# ProjectSchematic_v28.net
KiCad netlist of a schematic drawn in EAGLE
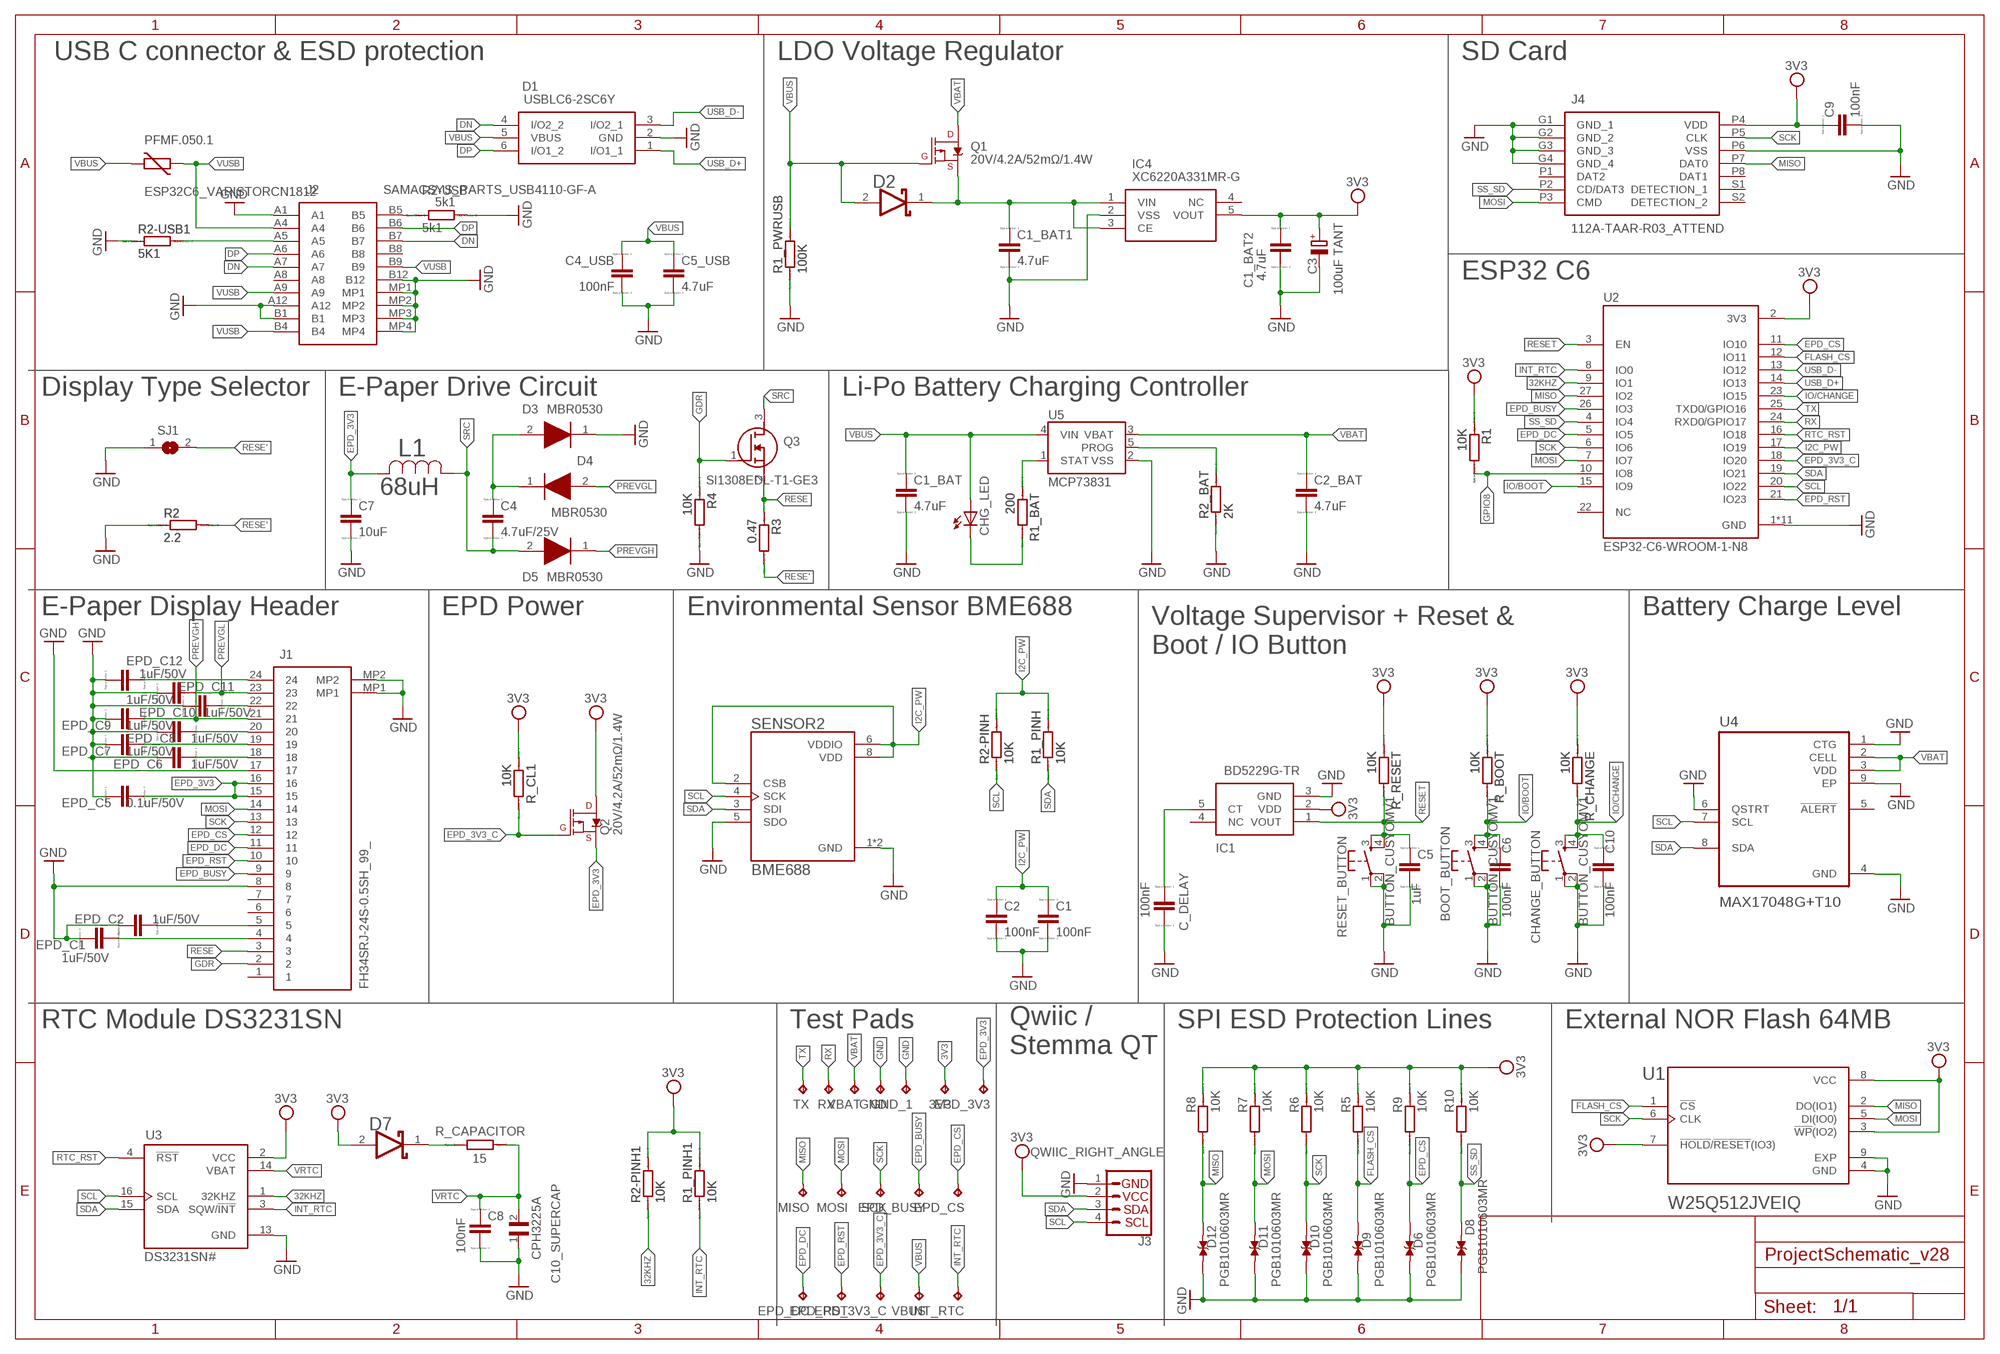
[diagram p0: schematic, sheet 1]

(export (version "E")
  (design (tool "Eeschema 10.0.6"))
  (components
    (comp (ref "3V3")
      (value "TPTP20R")
      (footprint "eagle-import:TP20R")
      (libsource (lib "eagle-import") (part "TPTP20R"))
    )
    (comp (ref "BOOT_BUTTON")
      (value "BUTTON_CUSYOMV1")
      (footprint "eagle-import:MYBUTTON")
      (libsource (lib "eagle-import") (part "BUTTON_CUSYOMV1"))
    )
    (comp (ref "C1")
      (value "100nF")
      (footprint "eagle-import:ESP32_WROVER_EAGLE-LTSPICE_C0402")
      (libsource (lib "eagle-import") (part "ESP32_WROVER_EAGLE-LTSPICE_CC0402"))
    )
    (comp (ref "C1_BAT")
      (value "4.7uF")
      (footprint "eagle-import:ESP32_WROVER_EAGLE-LTSPICE_C0402")
      (libsource (lib "eagle-import") (part "ESP32_WROVER_EAGLE-LTSPICE_CC0402"))
    )
    (comp (ref "C1_BAT1")
      (value "4.7uF")
      (footprint "eagle-import:ESP32_WROVER_EAGLE-LTSPICE_C0402")
      (libsource (lib "eagle-import") (part "ESP32_WROVER_EAGLE-LTSPICE_CC0402"))
    )
    (comp (ref "C1_BAT2")
      (value "4.7uF")
      (footprint "eagle-import:ESP32_WROVER_EAGLE-LTSPICE_C0402")
      (libsource (lib "eagle-import") (part "ESP32_WROVER_EAGLE-LTSPICE_CC0402"))
    )
    (comp (ref "C2")
      (value "100nF")
      (footprint "eagle-import:ESP32_WROVER_EAGLE-LTSPICE_C0402")
      (libsource (lib "eagle-import") (part "ESP32_WROVER_EAGLE-LTSPICE_CC0402"))
    )
    (comp (ref "C2_BAT")
      (value "4.7uF")
      (footprint "eagle-import:ESP32_WROVER_EAGLE-LTSPICE_C0402")
      (libsource (lib "eagle-import") (part "ESP32_WROVER_EAGLE-LTSPICE_CC0402"))
    )
    (comp (ref "C3")
      (value "100uF TANT")
      (footprint "eagle-import:RCL_CT3528")
      (libsource (lib "eagle-import") (part "RCL_CPOL-EUCT3528"))
    )
    (comp (ref "C4")
      (value "4.7uF/25V")
      (footprint "eagle-import:ESP32_WROVER_EAGLE-LTSPICE_C0402")
      (libsource (lib "eagle-import") (part "ESP32_WROVER_EAGLE-LTSPICE_CC0402"))
    )
    (comp (ref "C4_USB")
      (value "100nF")
      (footprint "eagle-import:ESP32_WROVER_EAGLE-LTSPICE_C0402")
      (libsource (lib "eagle-import") (part "ESP32_WROVER_EAGLE-LTSPICE_CC0402"))
    )
    (comp (ref "C5")
      (value "1uF")
      (footprint "eagle-import:ESP32_WROVER_EAGLE-LTSPICE_C0402")
      (libsource (lib "eagle-import") (part "ESP32_WROVER_EAGLE-LTSPICE_CC0402"))
    )
    (comp (ref "C5_USB")
      (value "4.7uF")
      (footprint "eagle-import:ESP32_WROVER_EAGLE-LTSPICE_C0402")
      (libsource (lib "eagle-import") (part "ESP32_WROVER_EAGLE-LTSPICE_CC0402"))
    )
    (comp (ref "C6")
      (value "100nF")
      (footprint "eagle-import:ESP32_WROVER_EAGLE-LTSPICE_C0402")
      (libsource (lib "eagle-import") (part "ESP32_WROVER_EAGLE-LTSPICE_CC0402"))
    )
    (comp (ref "C7")
      (value "10uF")
      (footprint "eagle-import:ESP32_WROVER_EAGLE-LTSPICE_C0402")
      (libsource (lib "eagle-import") (part "ESP32_WROVER_EAGLE-LTSPICE_CC0402"))
    )
    (comp (ref "C8")
      (value "100nF")
      (footprint "eagle-import:ESP32_WROVER_EAGLE-LTSPICE_C0402")
      (libsource (lib "eagle-import") (part "ESP32_WROVER_EAGLE-LTSPICE_CC0402"))
    )
    (comp (ref "C9")
      (value "100nF")
      (footprint "eagle-import:ESP32_WROVER_EAGLE-LTSPICE_C0402")
      (libsource (lib "eagle-import") (part "ESP32_WROVER_EAGLE-LTSPICE_CC0402"))
    )
    (comp (ref "C10")
      (value "100nF")
      (footprint "eagle-import:ESP32_WROVER_EAGLE-LTSPICE_C0402")
      (libsource (lib "eagle-import") (part "ESP32_WROVER_EAGLE-LTSPICE_CC0402"))
    )
    (comp (ref "C10_SUPERCAP")
      (value "CPH3225A")
      (footprint "eagle-import:CAPCP3225X100N")
      (fields (field (name "MF") "Seiko Instruments"))
      (libsource (lib "eagle-import") (part "CPH3225A"))
    )
    (comp (ref "CHANGE_BUTTON")
      (value "BUTTON_CUSYOMV1")
      (footprint "eagle-import:MYBUTTON")
      (libsource (lib "eagle-import") (part "BUTTON_CUSYOMV1"))
    )
    (comp (ref "CHG_LED")
      (value "ADAFRUIT_LEDCHIP-LED0603")
      (footprint "eagle-import:ADAFRUIT_CHIP-LED0603")
      (libsource (lib "eagle-import") (part "ADAFRUIT_LEDCHIP-LED0603"))
    )
    (comp (ref "C_DELAY")
      (value "100nF")
      (footprint "eagle-import:ESP32_WROVER_EAGLE-LTSPICE_C0402")
      (libsource (lib "eagle-import") (part "ESP32_WROVER_EAGLE-LTSPICE_CC0402"))
    )
    (comp (ref "D1")
      (value "USBLC6-2SC6Y")
      (footprint "eagle-import:SOT95P280X145-6N")
      (fields (field (name "MF") "STMicroelectronics"))
      (libsource (lib "eagle-import") (part "USBLC6-2SC6Y"))
    )
    (comp (ref "D2")
      (value "ESP32_WROVER_AVX---SD0805S020S1R0_AVX_SD0805S020S1R0_0_0AVX_SD0805S020S1R0_0_0")
      (footprint "eagle-import:ESP32_WROVER_AVX---SD0805S020S1R0_AVX_SD0805S020S1R0_0")
      (fields
        (field (name "DIGIKEY_PART_NUMBER") "478-7800-1-ND")
        (field (name "MF") "AVX")
        (field (name "MOUSER_PART_NUMBER") "581-SD0805S020S1R0")
      )
      (libsource (lib "eagle-import") (part "ESP32_WROVER_AVX---SD0805S020S1R0_AVX_SD0805S020S1R0_0_0AVX_SD0805S020S1R0_0_0"))
    )
    (comp (ref "D3")
      (value "MBR0530")
      (footprint "eagle-import:SOD3716X135N")
      (fields (field (name "MF") "ON Semiconductor"))
      (libsource (lib "eagle-import") (part "MBR0530"))
    )
    (comp (ref "D4")
      (value "MBR0530")
      (footprint "eagle-import:SOD3716X135N")
      (fields (field (name "MF") "ON Semiconductor"))
      (libsource (lib "eagle-import") (part "MBR0530"))
    )
    (comp (ref "D5")
      (value "MBR0530")
      (footprint "eagle-import:SOD3716X135N")
      (fields (field (name "MF") "ON Semiconductor"))
      (libsource (lib "eagle-import") (part "MBR0530"))
    )
    (comp (ref "D6")
      (value "PGB1010603MR")
      (footprint "eagle-import:DIOC1608X36N")
      (fields (field (name "MF") "Littelfuse Inc."))
      (libsource (lib "eagle-import") (part "PGB1010603MR"))
    )
    (comp (ref "D7")
      (value "ESP32_WROVER_AVX---SD0805S020S1R0_AVX_SD0805S020S1R0_0_0AVX_SD0805S020S1R0_0_0")
      (footprint "eagle-import:ESP32_WROVER_AVX---SD0805S020S1R0_AVX_SD0805S020S1R0_0")
      (fields
        (field (name "DIGIKEY_PART_NUMBER") "478-7800-1-ND")
        (field (name "MF") "AVX")
        (field (name "MOUSER_PART_NUMBER") "581-SD0805S020S1R0")
      )
      (libsource (lib "eagle-import") (part "ESP32_WROVER_AVX---SD0805S020S1R0_AVX_SD0805S020S1R0_0_0AVX_SD0805S020S1R0_0_0"))
    )
    (comp (ref "D8")
      (value "PGB1010603MR")
      (footprint "eagle-import:DIOC1608X36N")
      (fields (field (name "MF") "Littelfuse Inc."))
      (libsource (lib "eagle-import") (part "PGB1010603MR"))
    )
    (comp (ref "D9")
      (value "PGB1010603MR")
      (footprint "eagle-import:DIOC1608X36N")
      (fields (field (name "MF") "Littelfuse Inc."))
      (libsource (lib "eagle-import") (part "PGB1010603MR"))
    )
    (comp (ref "D10")
      (value "PGB1010603MR")
      (footprint "eagle-import:DIOC1608X36N")
      (fields (field (name "MF") "Littelfuse Inc."))
      (libsource (lib "eagle-import") (part "PGB1010603MR"))
    )
    (comp (ref "D11")
      (value "PGB1010603MR")
      (footprint "eagle-import:DIOC1608X36N")
      (fields (field (name "MF") "Littelfuse Inc."))
      (libsource (lib "eagle-import") (part "PGB1010603MR"))
    )
    (comp (ref "D12")
      (value "PGB1010603MR")
      (footprint "eagle-import:DIOC1608X36N")
      (fields (field (name "MF") "Littelfuse Inc."))
      (libsource (lib "eagle-import") (part "PGB1010603MR"))
    )
    (comp (ref "EPD_3V3")
      (value "TPTP20R")
      (footprint "eagle-import:TP20R")
      (libsource (lib "eagle-import") (part "TPTP20R"))
    )
    (comp (ref "EPD_3V3_C")
      (value "TPTP20R")
      (footprint "eagle-import:TP20R")
      (libsource (lib "eagle-import") (part "TPTP20R"))
    )
    (comp (ref "EPD_BUSY")
      (value "TPTP20R")
      (footprint "eagle-import:TP20R")
      (libsource (lib "eagle-import") (part "TPTP20R"))
    )
    (comp (ref "EPD_C1")
      (value "1uF/50V")
      (footprint "eagle-import:ESP32_WROVER_EAGLE-LTSPICE_C0402")
      (libsource (lib "eagle-import") (part "ESP32_WROVER_EAGLE-LTSPICE_CC0402"))
    )
    (comp (ref "EPD_C2")
      (value "1uF/50V")
      (footprint "eagle-import:ESP32_WROVER_EAGLE-LTSPICE_C0402")
      (libsource (lib "eagle-import") (part "ESP32_WROVER_EAGLE-LTSPICE_CC0402"))
    )
    (comp (ref "EPD_C5")
      (value "0.1uF/50V")
      (footprint "eagle-import:ESP32_WROVER_EAGLE-LTSPICE_C0402")
      (libsource (lib "eagle-import") (part "ESP32_WROVER_EAGLE-LTSPICE_CC0402"))
    )
    (comp (ref "EPD_C6")
      (value "1uF/50V")
      (footprint "eagle-import:ESP32_WROVER_EAGLE-LTSPICE_C0402")
      (libsource (lib "eagle-import") (part "ESP32_WROVER_EAGLE-LTSPICE_CC0402"))
    )
    (comp (ref "EPD_C7")
      (value "1uF/50V")
      (footprint "eagle-import:ESP32_WROVER_EAGLE-LTSPICE_C0402")
      (libsource (lib "eagle-import") (part "ESP32_WROVER_EAGLE-LTSPICE_CC0402"))
    )
    (comp (ref "EPD_C8")
      (value "1uF/50V")
      (footprint "eagle-import:ESP32_WROVER_EAGLE-LTSPICE_C0402")
      (libsource (lib "eagle-import") (part "ESP32_WROVER_EAGLE-LTSPICE_CC0402"))
    )
    (comp (ref "EPD_C9")
      (value "1uF/50V")
      (footprint "eagle-import:ESP32_WROVER_EAGLE-LTSPICE_C0402")
      (libsource (lib "eagle-import") (part "ESP32_WROVER_EAGLE-LTSPICE_CC0402"))
    )
    (comp (ref "EPD_C10")
      (value "1uF/50V")
      (footprint "eagle-import:ESP32_WROVER_EAGLE-LTSPICE_C0402")
      (libsource (lib "eagle-import") (part "ESP32_WROVER_EAGLE-LTSPICE_CC0402"))
    )
    (comp (ref "EPD_C11")
      (value "1uF/50V")
      (footprint "eagle-import:ESP32_WROVER_EAGLE-LTSPICE_C0402")
      (libsource (lib "eagle-import") (part "ESP32_WROVER_EAGLE-LTSPICE_CC0402"))
    )
    (comp (ref "EPD_C12")
      (value "1uF/50V")
      (footprint "eagle-import:ESP32_WROVER_EAGLE-LTSPICE_C0402")
      (libsource (lib "eagle-import") (part "ESP32_WROVER_EAGLE-LTSPICE_CC0402"))
    )
    (comp (ref "EPD_CS")
      (value "TPTP20R")
      (footprint "eagle-import:TP20R")
      (libsource (lib "eagle-import") (part "TPTP20R"))
    )
    (comp (ref "EPD_DC")
      (value "TPTP20R")
      (footprint "eagle-import:TP20R")
      (libsource (lib "eagle-import") (part "TPTP20R"))
    )
    (comp (ref "EPD_RST")
      (value "TPTP20R")
      (footprint "eagle-import:TP20R")
      (libsource (lib "eagle-import") (part "TPTP20R"))
    )
    (comp (ref "GND")
      (value "TPTP20R")
      (footprint "eagle-import:TP20R")
      (libsource (lib "eagle-import") (part "TPTP20R"))
    )
    (comp (ref "GND_1")
      (value "TPTP20R")
      (footprint "eagle-import:TP20R")
      (libsource (lib "eagle-import") (part "TPTP20R"))
    )
    (comp (ref "IC1")
      (value "BD5229G-TR")
      (footprint "eagle-import:SOT95P280X125-5N")
      (fields (field (name "MOUSER_PART_NUMBER") "755-BD5229G-TR"))
      (libsource (lib "eagle-import") (part "BD5229G-TR"))
    )
    (comp (ref "IC4")
      (value "XC6220A331MR-G")
      (footprint "eagle-import:SOT95P280X120-5N")
      (fields (field (name "MOUSER_PART_NUMBER") "865-XC6220A331MR-G"))
      (libsource (lib "eagle-import") (part "XC6220A331MR-G"))
    )
    (comp (ref "INT_RTC")
      (value "TPTP20R")
      (footprint "eagle-import:TP20R")
      (libsource (lib "eagle-import") (part "TPTP20R"))
    )
    (comp (ref "J1")
      (value "FH34SRJ-24S-0.5SH_99_")
      (footprint "eagle-import:FH34SRJ24S05SH99")
      (fields
        (field (name "MANUFACTURER_PART_NUMBER") "FH34SRJ-24S-0.5SH(99)")
        (field (name "MOUSER_PART_NUMBER") "798-FH34SRJ24S05SH99")
      )
      (libsource (lib "eagle-import") (part "FH34SRJ-24S-0.5SH_99_"))
    )
    (comp (ref "J2")
      (value "SAMACSYS_PARTS_USB4110-GF-A")
      (footprint "eagle-import:SAMACSYS_PARTS_USB4110GFA")
      (fields
        (field (name "MANUFACTURER_PART_NUMBER") "USB4110-GF-A")
        (field (name "MOUSER_PART_NUMBER") "640-USB4110-GF-A")
      )
      (libsource (lib "eagle-import") (part "SAMACSYS_PARTS_USB4110-GF-A"))
    )
    (comp (ref "J3")
      (value "QWIIC_RIGHT_ANGLE")
      (footprint "eagle-import:JST04_1MM_RA")
      (libsource (lib "eagle-import") (part "QWIIC_CONNECTORJS-1MM"))
    )
    (comp (ref "J4")
      (value "112A-TAAR-R03_ATTEND")
      (footprint "eagle-import:112ATAARR03ATTEND")
      (fields (field (name "MANUFACTURER_PART_NUMBER") "112A-TAAR-R03 ATTEND"))
      (libsource (lib "eagle-import") (part "112A-TAAR-R03_ATTEND"))
    )
    (comp (ref "L1")
      (value "68uH")
      (footprint "eagle-import:IND_4828-WE-TPC_WRE")
      (fields
        (field (name "MANUFACTURER_PART_NUMBER") "744043680")
        (field (name "COPYRIGHT") "Copyright (C) 2024 Ultra Librarian. All rights reserved.")
      )
      (libsource (lib "eagle-import") (part "744043680IND_4828-WE-TPC_WRE"))
    )
    (comp (ref "MISO")
      (value "TPTP20R")
      (footprint "eagle-import:TP20R")
      (libsource (lib "eagle-import") (part "TPTP20R"))
    )
    (comp (ref "MOSI")
      (value "TPTP20R")
      (footprint "eagle-import:TP20R")
      (libsource (lib "eagle-import") (part "TPTP20R"))
    )
    (comp (ref "PFMF.050.1")
      (value "ESP32C6_VARISTORCN1812")
      (footprint "eagle-import:ESP32C6_VARISTOR_CT_CN1812")
      (libsource (lib "eagle-import") (part "ESP32C6_VARISTORCN1812"))
    )
    (comp (ref "Q1")
      (value "20V/4.2A/52mΩ/1.4W")
      (footprint "eagle-import:ESP32_WROVER_SPARKFUN-DISCRETESEMI_SOT23-3")
      (libsource (lib "eagle-import") (part "ESP32_WROVER_SPARKFUN-DISCRETESEMI_MOSFET_PCH-DMG2305UX-7"))
    )
    (comp (ref "Q2")
      (value "20V/4.2A/52mΩ/1.4W")
      (footprint "eagle-import:ESP32_WROVER_SPARKFUN-DISCRETESEMI_SOT23-3")
      (libsource (lib "eagle-import") (part "ESP32_WROVER_SPARKFUN-DISCRETESEMI_MOSFET_PCH-DMG2305UX-7"))
    )
    (comp (ref "Q3")
      (value "SI1308EDL-T1-GE3")
      (footprint "eagle-import:SOT65P210X110-3N")
      (fields (field (name "MF") "Vishay Siliconix"))
      (libsource (lib "eagle-import") (part "SI1308EDL-T1-GE3"))
    )
    (comp (ref "R1")
      (value "10K")
      (footprint "eagle-import:ESP32_WROVER_EAGLE-LTSPICE_R0402")
      (libsource (lib "eagle-import") (part "ESP32_WROVER_EAGLE-LTSPICE_RR0402"))
    )
    (comp (ref "R1_BAT")
      (value "200")
      (footprint "eagle-import:ESP32_WROVER_EAGLE-LTSPICE_R0402")
      (libsource (lib "eagle-import") (part "ESP32_WROVER_EAGLE-LTSPICE_RR0402"))
    )
    (comp (ref "R1_PINH")
      (value "10K")
      (footprint "eagle-import:ESP32_WROVER_EAGLE-LTSPICE_R0402")
      (libsource (lib "eagle-import") (part "ESP32_WROVER_EAGLE-LTSPICE_RR0402"))
    )
    (comp (ref "R1_PINH1")
      (value "10K")
      (footprint "eagle-import:ESP32_WROVER_EAGLE-LTSPICE_R0402")
      (libsource (lib "eagle-import") (part "ESP32_WROVER_EAGLE-LTSPICE_RR0402"))
    )
    (comp (ref "R1_PWRUSB")
      (value "100K")
      (footprint "eagle-import:ESP32_WROVER_EAGLE-LTSPICE_R0402")
      (libsource (lib "eagle-import") (part "ESP32_WROVER_EAGLE-LTSPICE_RR0402"))
    )
    (comp (ref "R2")
      (value "2.2")
      (footprint "eagle-import:ESP32_WROVER_EAGLE-LTSPICE_R0402")
      (libsource (lib "eagle-import") (part "ESP32_WROVER_EAGLE-LTSPICE_RR0402"))
    )
    (comp (ref "R2-PINH")
      (value "10K")
      (footprint "eagle-import:ESP32_WROVER_EAGLE-LTSPICE_R0402")
      (libsource (lib "eagle-import") (part "ESP32_WROVER_EAGLE-LTSPICE_RR0402"))
    )
    (comp (ref "R2-PINH1")
      (value "10K")
      (footprint "eagle-import:ESP32_WROVER_EAGLE-LTSPICE_R0402")
      (libsource (lib "eagle-import") (part "ESP32_WROVER_EAGLE-LTSPICE_RR0402"))
    )
    (comp (ref "R2-USB")
      (value "5k1")
      (footprint "eagle-import:ESP32_WROVER_EAGLE-LTSPICE_R0402")
      (libsource (lib "eagle-import") (part "ESP32_WROVER_EAGLE-LTSPICE_RR0402"))
    )
    (comp (ref "R2-USB1")
      (value "5K1")
      (footprint "eagle-import:ESP32_WROVER_EAGLE-LTSPICE_R0402")
      (libsource (lib "eagle-import") (part "ESP32_WROVER_EAGLE-LTSPICE_RR0402"))
    )
    (comp (ref "R2_BAT")
      (value "2K")
      (footprint "eagle-import:ESP32_WROVER_EAGLE-LTSPICE_R0402")
      (libsource (lib "eagle-import") (part "ESP32_WROVER_EAGLE-LTSPICE_RR0402"))
    )
    (comp (ref "R3")
      (value "0.47")
      (footprint "eagle-import:ESP32_WROVER_EAGLE-LTSPICE_R0402")
      (libsource (lib "eagle-import") (part "ESP32_WROVER_EAGLE-LTSPICE_RR0402"))
    )
    (comp (ref "R4")
      (value "10K")
      (footprint "eagle-import:ESP32_WROVER_EAGLE-LTSPICE_R0402")
      (libsource (lib "eagle-import") (part "ESP32_WROVER_EAGLE-LTSPICE_RR0402"))
    )
    (comp (ref "R5")
      (value "10K")
      (footprint "eagle-import:ESP32_WROVER_EAGLE-LTSPICE_R0402")
      (libsource (lib "eagle-import") (part "ESP32_WROVER_EAGLE-LTSPICE_RR0402"))
    )
    (comp (ref "R6")
      (value "10K")
      (footprint "eagle-import:ESP32_WROVER_EAGLE-LTSPICE_R0402")
      (libsource (lib "eagle-import") (part "ESP32_WROVER_EAGLE-LTSPICE_RR0402"))
    )
    (comp (ref "R7")
      (value "10K")
      (footprint "eagle-import:ESP32_WROVER_EAGLE-LTSPICE_R0402")
      (libsource (lib "eagle-import") (part "ESP32_WROVER_EAGLE-LTSPICE_RR0402"))
    )
    (comp (ref "R8")
      (value "10K")
      (footprint "eagle-import:ESP32_WROVER_EAGLE-LTSPICE_R0402")
      (libsource (lib "eagle-import") (part "ESP32_WROVER_EAGLE-LTSPICE_RR0402"))
    )
    (comp (ref "R9")
      (value "10K")
      (footprint "eagle-import:ESP32_WROVER_EAGLE-LTSPICE_R0402")
      (libsource (lib "eagle-import") (part "ESP32_WROVER_EAGLE-LTSPICE_RR0402"))
    )
    (comp (ref "R10")
      (value "10K")
      (footprint "eagle-import:ESP32_WROVER_EAGLE-LTSPICE_R0402")
      (libsource (lib "eagle-import") (part "ESP32_WROVER_EAGLE-LTSPICE_RR0402"))
    )
    (comp (ref "RESET_BUTTON")
      (value "BUTTON_CUSYOMV1")
      (footprint "eagle-import:MYBUTTON")
      (libsource (lib "eagle-import") (part "BUTTON_CUSYOMV1"))
    )
    (comp (ref "RX")
      (value "TPTP20R")
      (footprint "eagle-import:TP20R")
      (libsource (lib "eagle-import") (part "TPTP20R"))
    )
    (comp (ref "R_BOOT")
      (value "10K")
      (footprint "eagle-import:ESP32_WROVER_EAGLE-LTSPICE_R0402")
      (libsource (lib "eagle-import") (part "ESP32_WROVER_EAGLE-LTSPICE_RR0402"))
    )
    (comp (ref "R_CAPACITOR")
      (value "15")
      (footprint "eagle-import:ESP32_WROVER_EAGLE-LTSPICE_R0402")
      (libsource (lib "eagle-import") (part "ESP32_WROVER_EAGLE-LTSPICE_RR0402"))
    )
    (comp (ref "R_CHANGE")
      (value "10K")
      (footprint "eagle-import:ESP32_WROVER_EAGLE-LTSPICE_R0402")
      (libsource (lib "eagle-import") (part "ESP32_WROVER_EAGLE-LTSPICE_RR0402"))
    )
    (comp (ref "R_CL1")
      (value "10K")
      (footprint "eagle-import:ESP32_WROVER_EAGLE-LTSPICE_R0402")
      (libsource (lib "eagle-import") (part "ESP32_WROVER_EAGLE-LTSPICE_RR0402"))
    )
    (comp (ref "R_RESET")
      (value "10K")
      (footprint "eagle-import:ESP32_WROVER_EAGLE-LTSPICE_R0402")
      (libsource (lib "eagle-import") (part "ESP32_WROVER_EAGLE-LTSPICE_RR0402"))
    )
    (comp (ref "SCK")
      (value "TPTP20R")
      (footprint "eagle-import:TP20R")
      (libsource (lib "eagle-import") (part "TPTP20R"))
    )
    (comp (ref "SENSOR2")
      (value "BME688")
      (footprint "eagle-import:ESP32_WROVER_BME680_PSON80P300X300X100-8N")
      (fields (field (name "MF") "Bosch Sensortec") (field (name "MP") "BME680"))
      (libsource (lib "eagle-import") (part "ESP32_WROVER_BME680_BME680"))
    )
    (comp (ref "SJ1") (value "SJ") (footprint "eagle-import:SJ") (libsource (lib "eagle-import") (part "SJ")))
    (comp (ref "TX")
      (value "TPTP20R")
      (footprint "eagle-import:TP20R")
      (libsource (lib "eagle-import") (part "TPTP20R"))
    )
    (comp (ref "U1")
      (value "W25Q512JVEIQ")
      (footprint "eagle-import:SON127P600X800X80-9N")
      (fields (field (name "MF") "Winbond Electronics"))
      (libsource (lib "eagle-import") (part "W25Q512JVEIQ"))
    )
    (comp (ref "U2")
      (value "ESP32-C6-WROOM-1-N8")
      (footprint "eagle-import:XCVR_ESP32-C6-WROOM-1-N8")
      (fields (field (name "MF") "Espressif Systems"))
      (libsource (lib "eagle-import") (part "ESP32-C6-WROOM-1-N8"))
    )
    (comp (ref "U3")
      (value "DS3231SN#")
      (footprint "eagle-import:SOIC127P1032X265-16N")
      (fields (field (name "MF") "Analog Devices"))
      (libsource (lib "eagle-import") (part "DS3231SN#"))
    )
    (comp (ref "U4")
      (value "MAX17048G+T10")
      (footprint "eagle-import:SON50P200X200X80-9N")
      (fields (field (name "MF") "Analog Devices"))
      (libsource (lib "eagle-import") (part "MAX17048G+T10"))
    )
    (comp (ref "U5")
      (value "MCP73831")
      (footprint "eagle-import:ESP32_WROVER_SPARKFUN-IC-POWER_SOT23-5")
      (libsource (lib "eagle-import") (part "ESP32_WROVER_SPARKFUN-IC-POWER_MCP73831"))
    )
    (comp (ref "VBAT")
      (value "TPTP20R")
      (footprint "eagle-import:TP20R")
      (libsource (lib "eagle-import") (part "TPTP20R"))
    )
    (comp (ref "VBUS")
      (value "TPTP20R")
      (footprint "eagle-import:TP20R")
      (libsource (lib "eagle-import") (part "TPTP20R"))
    )
  )
  (nets
    (net (code "1") (name "3V3") (class "Default")
      (node (ref "3V3") (pin "TP") (pinfunction "TP_TP") (pintype "input"))
      (node (ref "C1_BAT2") (pin "1") (pinfunction "1_1") (pintype "passive"))
      (node (ref "C3") (pin "+") (pinfunction "+_+") (pintype "passive"))
      (node (ref "C9") (pin "1") (pinfunction "1_1") (pintype "passive"))
      (node (ref "D7") (pin "2") (pinfunction "ANODE_2") (pintype "bidirectional"))
      (node (ref "IC1") (pin "2") (pinfunction "VDD_2") (pintype "bidirectional"))
      (node (ref "IC4") (pin "5") (pinfunction "VOUT_5") (pintype "bidirectional"))
      (node (ref "J3") (pin "2") (pinfunction "2_2") (pintype "power_in"))
      (node (ref "J4") (pin "P4") (pinfunction "VDD_P4") (pintype "bidirectional"))
      (node (ref "Q2") (pin "3") (pinfunction "D_3") (pintype "bidirectional"))
      (node (ref "R1") (pin "1") (pinfunction "1_1") (pintype "passive"))
      (node (ref "R10") (pin "2") (pinfunction "2_2") (pintype "passive"))
      (node (ref "R1_PINH1") (pin "2") (pinfunction "2_2") (pintype "passive"))
      (node (ref "R2-PINH1") (pin "2") (pinfunction "2_2") (pintype "passive"))
      (node (ref "R5") (pin "2") (pinfunction "2_2") (pintype "passive"))
      (node (ref "R6") (pin "2") (pinfunction "2_2") (pintype "passive"))
      (node (ref "R7") (pin "2") (pinfunction "2_2") (pintype "passive"))
      (node (ref "R8") (pin "2") (pinfunction "2_2") (pintype "passive"))
      (node (ref "R9") (pin "2") (pinfunction "2_2") (pintype "passive"))
      (node (ref "R_BOOT") (pin "1") (pinfunction "1_1") (pintype "passive"))
      (node (ref "R_CHANGE") (pin "1") (pinfunction "1_1") (pintype "passive"))
      (node (ref "R_CL1") (pin "1") (pinfunction "1_1") (pintype "passive"))
      (node (ref "R_RESET") (pin "1") (pinfunction "1_1") (pintype "passive"))
      (node (ref "U1") (pin "3") (pinfunction "~{WP}(IO2)_3") (pintype "bidirectional"))
      (node (ref "U1") (pin "7") (pinfunction "~{HOLD}/~{RESET}(IO3)_7") (pintype "bidirectional"))
      (node (ref "U1") (pin "8") (pinfunction "VCC_8") (pintype "power_in"))
      (node (ref "U2") (pin "2") (pinfunction "3V3_2") (pintype "power_in"))
      (node (ref "U3") (pin "2") (pinfunction "VCC_2") (pintype "power_in"))
    )
    (net (code "2") (name "32KHZ") (class "Default")
      (node (ref "R2-PINH1") (pin "1") (pinfunction "1_1") (pintype "passive"))
      (node (ref "U2") (pin "9") (pinfunction "IO1_9") (pintype "bidirectional"))
      (node (ref "U3") (pin "1") (pinfunction "32KHZ_1") (pintype "output"))
    )
    (net (code "3") (name "DN") (class "Default")
      (node (ref "D1") (pin "4") (pinfunction "I/O2_2_4") (pintype "bidirectional"))
      (node (ref "J2") (pin "A7") (pinfunction "A7_A7") (pintype "bidirectional"))
      (node (ref "J2") (pin "B7") (pinfunction "B7_B7") (pintype "bidirectional"))
    )
    (net (code "4") (name "DP") (class "Default")
      (node (ref "D1") (pin "6") (pinfunction "I/O1_2_6") (pintype "bidirectional"))
      (node (ref "J2") (pin "A6") (pinfunction "A6_A6") (pintype "bidirectional"))
      (node (ref "J2") (pin "B6") (pinfunction "B6_B6") (pintype "bidirectional"))
    )
    (net (code "5") (name "EPD_3V3") (class "Default")
      (node (ref "C7") (pin "1") (pinfunction "1_1") (pintype "passive"))
      (node (ref "EPD_3V3") (pin "TP") (pinfunction "TP_TP") (pintype "input"))
      (node (ref "EPD_C5") (pin "2") (pinfunction "2_2") (pintype "passive"))
      (node (ref "J1") (pin "15") (pinfunction "15_15") (pintype "bidirectional"))
      (node (ref "J1") (pin "16") (pinfunction "16_16") (pintype "bidirectional"))
      (node (ref "L1") (pin "2") (pinfunction "2_2") (pintype "passive"))
      (node (ref "Q2") (pin "2") (pinfunction "S_2") (pintype "bidirectional"))
    )
    (net (code "6") (name "EPD_3V3_C") (class "Default")
      (node (ref "EPD_3V3_C") (pin "TP") (pinfunction "TP_TP") (pintype "input"))
      (node (ref "Q2") (pin "1") (pinfunction "G_1") (pintype "bidirectional"))
      (node (ref "R_CL1") (pin "2") (pinfunction "2_2") (pintype "passive"))
      (node (ref "U2") (pin "18") (pinfunction "IO20_18") (pintype "bidirectional"))
    )
    (net (code "7") (name "EPD_BUSY") (class "Default")
      (node (ref "EPD_BUSY") (pin "TP") (pinfunction "TP_TP") (pintype "input"))
      (node (ref "J1") (pin "9") (pinfunction "9_9") (pintype "bidirectional"))
      (node (ref "U2") (pin "26") (pinfunction "IO3_26") (pintype "bidirectional"))
    )
    (net (code "8") (name "EPD_CS") (class "Default")
      (node (ref "D6") (pin "2") (pinfunction "2_2") (pintype "passive"))
      (node (ref "EPD_CS") (pin "TP") (pinfunction "TP_TP") (pintype "input"))
      (node (ref "J1") (pin "12") (pinfunction "12_12") (pintype "bidirectional"))
      (node (ref "R9") (pin "1") (pinfunction "1_1") (pintype "passive"))
      (node (ref "U2") (pin "11") (pinfunction "IO10_11") (pintype "bidirectional"))
    )
    (net (code "9") (name "EPD_DC") (class "Default")
      (node (ref "EPD_DC") (pin "TP") (pinfunction "TP_TP") (pintype "input"))
      (node (ref "J1") (pin "11") (pinfunction "11_11") (pintype "bidirectional"))
      (node (ref "U2") (pin "5") (pinfunction "IO5_5") (pintype "bidirectional"))
    )
    (net (code "10") (name "EPD_RST") (class "Default")
      (node (ref "EPD_RST") (pin "TP") (pinfunction "TP_TP") (pintype "input"))
      (node (ref "J1") (pin "10") (pinfunction "10_10") (pintype "bidirectional"))
      (node (ref "U2") (pin "21") (pinfunction "IO23_21") (pintype "bidirectional"))
    )
    (net (code "11") (name "FLASH_CS") (class "Default")
      (node (ref "D9") (pin "2") (pinfunction "2_2") (pintype "passive"))
      (node (ref "R5") (pin "1") (pinfunction "1_1") (pintype "passive"))
      (node (ref "U1") (pin "1") (pinfunction "~{CS}_1") (pintype "input"))
      (node (ref "U2") (pin "12") (pinfunction "IO11_12") (pintype "bidirectional"))
    )
    (net (code "12") (name "GDR") (class "Default")
      (node (ref "J1") (pin "2") (pinfunction "2_2") (pintype "bidirectional"))
      (node (ref "Q3") (pin "1") (pinfunction "G_1") (pintype "bidirectional"))
      (node (ref "R4") (pin "1") (pinfunction "1_1") (pintype "passive"))
    )
    (net (code "13") (name "GND") (class "Default")
      (node (ref "BOOT_BUTTON") (pin "1") (pinfunction "1_1") (pintype "passive"))
      (node (ref "BOOT_BUTTON") (pin "2") (pinfunction "2_2") (pintype "passive"))
      (node (ref "C1") (pin "2") (pinfunction "2_2") (pintype "passive"))
      (node (ref "C10") (pin "2") (pinfunction "2_2") (pintype "passive"))
      (node (ref "C10_SUPERCAP") (pin "1") (pinfunction "1_1") (pintype "passive"))
      (node (ref "C1_BAT") (pin "2") (pinfunction "2_2") (pintype "passive"))
      (node (ref "C1_BAT1") (pin "2") (pinfunction "2_2") (pintype "passive"))
      (node (ref "C1_BAT2") (pin "2") (pinfunction "2_2") (pintype "passive"))
      (node (ref "C2") (pin "2") (pinfunction "2_2") (pintype "passive"))
      (node (ref "C2_BAT") (pin "2") (pinfunction "2_2") (pintype "passive"))
      (node (ref "C3") (pin "-") (pinfunction "-_-") (pintype "passive"))
      (node (ref "C4_USB") (pin "2") (pinfunction "2_2") (pintype "passive"))
      (node (ref "C5") (pin "2") (pinfunction "2_2") (pintype "passive"))
      (node (ref "C5_USB") (pin "2") (pinfunction "2_2") (pintype "passive"))
      (node (ref "C6") (pin "2") (pinfunction "2_2") (pintype "passive"))
      (node (ref "C7") (pin "2") (pinfunction "2_2") (pintype "passive"))
      (node (ref "C8") (pin "2") (pinfunction "2_2") (pintype "passive"))
      (node (ref "C9") (pin "2") (pinfunction "2_2") (pintype "passive"))
      (node (ref "CHANGE_BUTTON") (pin "1") (pinfunction "1_1") (pintype "passive"))
      (node (ref "CHANGE_BUTTON") (pin "2") (pinfunction "2_2") (pintype "passive"))
      (node (ref "C_DELAY") (pin "2") (pinfunction "2_2") (pintype "passive"))
      (node (ref "D1") (pin "2") (pinfunction "GND_2") (pintype "bidirectional"))
      (node (ref "D10") (pin "1") (pinfunction "1_1") (pintype "passive"))
      (node (ref "D11") (pin "1") (pinfunction "1_1") (pintype "passive"))
      (node (ref "D12") (pin "1") (pinfunction "1_1") (pintype "passive"))
      (node (ref "D3") (pin "1") (pinfunction "K_1") (pintype "bidirectional"))
      (node (ref "D6") (pin "1") (pinfunction "1_1") (pintype "passive"))
      (node (ref "D8") (pin "1") (pinfunction "1_1") (pintype "passive"))
      (node (ref "D9") (pin "1") (pinfunction "1_1") (pintype "passive"))
      (node (ref "EPD_C1") (pin "2") (pinfunction "2_2") (pintype "passive"))
      (node (ref "EPD_C10") (pin "1") (pinfunction "1_1") (pintype "passive"))
      (node (ref "EPD_C11") (pin "1") (pinfunction "1_1") (pintype "passive"))
      (node (ref "EPD_C12") (pin "1") (pinfunction "1_1") (pintype "passive"))
      (node (ref "EPD_C2") (pin "2") (pinfunction "2_2") (pintype "passive"))
      (node (ref "EPD_C5") (pin "1") (pinfunction "1_1") (pintype "passive"))
      (node (ref "EPD_C6") (pin "1") (pinfunction "1_1") (pintype "passive"))
      (node (ref "EPD_C7") (pin "1") (pinfunction "1_1") (pintype "passive"))
      (node (ref "EPD_C8") (pin "1") (pinfunction "1_1") (pintype "passive"))
      (node (ref "EPD_C9") (pin "1") (pinfunction "1_1") (pintype "passive"))
      (node (ref "GND") (pin "TP") (pinfunction "TP_TP") (pintype "input"))
      (node (ref "GND_1") (pin "TP") (pinfunction "TP_TP") (pintype "input"))
      (node (ref "IC1") (pin "3") (pinfunction "GND_3") (pintype "bidirectional"))
      (node (ref "IC4") (pin "2") (pinfunction "VSS_2") (pintype "bidirectional"))
      (node (ref "J1") (pin "17") (pinfunction "17_17") (pintype "bidirectional"))
      (node (ref "J1") (pin "8") (pinfunction "8_8") (pintype "bidirectional"))
      (node (ref "J1") (pin "MP1") (pinfunction "MP1_MP1") (pintype "bidirectional"))
      (node (ref "J1") (pin "MP2") (pinfunction "MP2_MP2") (pintype "bidirectional"))
      (node (ref "J2") (pin "A1") (pinfunction "A1_A1") (pintype "bidirectional"))
      (node (ref "J2") (pin "A12") (pinfunction "A12_A12") (pintype "bidirectional"))
      (node (ref "J2") (pin "B1") (pinfunction "B1_B1") (pintype "bidirectional"))
      (node (ref "J2") (pin "B12") (pinfunction "B12_B12") (pintype "bidirectional"))
      (node (ref "J2") (pin "MP1") (pinfunction "MP1_MP1") (pintype "bidirectional"))
      (node (ref "J2") (pin "MP2") (pinfunction "MP2_MP2") (pintype "bidirectional"))
      (node (ref "J2") (pin "MP3") (pinfunction "MP3_MP3") (pintype "bidirectional"))
      (node (ref "J2") (pin "MP4") (pinfunction "MP4_MP4") (pintype "bidirectional"))
      (node (ref "J3") (pin "1") (pinfunction "1_1") (pintype "power_in"))
      (node (ref "J4") (pin "G1") (pinfunction "GND_1_G1") (pintype "bidirectional"))
      (node (ref "J4") (pin "G2") (pinfunction "GND_2_G2") (pintype "bidirectional"))
      (node (ref "J4") (pin "G3") (pinfunction "GND_3_G3") (pintype "bidirectional"))
      (node (ref "J4") (pin "G4") (pinfunction "GND_4_G4") (pintype "bidirectional"))
      (node (ref "J4") (pin "P6") (pinfunction "VSS_P6") (pintype "bidirectional"))
      (node (ref "R1_PWRUSB") (pin "1") (pinfunction "1_1") (pintype "passive"))
      (node (ref "R2") (pin "1") (pinfunction "1_1") (pintype "passive"))
      (node (ref "R2-USB") (pin "2") (pinfunction "2_2") (pintype "passive"))
      (node (ref "R2-USB1") (pin "1") (pinfunction "1_1") (pintype "passive"))
      (node (ref "R2_BAT") (pin "1") (pinfunction "1_1") (pintype "passive"))
      (node (ref "R4") (pin "2") (pinfunction "2_2") (pintype "passive"))
      (node (ref "RESET_BUTTON") (pin "1") (pinfunction "1_1") (pintype "passive"))
      (node (ref "RESET_BUTTON") (pin "2") (pinfunction "2_2") (pintype "passive"))
      (node (ref "SENSOR2") (pin "1") (pinfunction "GND_1") (pintype "power_in"))
      (node (ref "SENSOR2") (pin "5") (pinfunction "SDO_5") (pintype "bidirectional"))
      (node (ref "SENSOR2") (pin "7") (pinfunction "GND_7") (pintype "power_in"))
      (node (ref "SJ1") (pin "1") (pinfunction "1_1") (pintype "passive"))
      (node (ref "U1") (pin "4") (pinfunction "GND_4") (pintype "power_in"))
      (node (ref "U1") (pin "9") (pinfunction "EXP_9") (pintype "passive"))
      (node (ref "U2") (pin "1") (pinfunction "GND_1") (pintype "power_in"))
      (node (ref "U2") (pin "28") (pinfunction "GND_28") (pintype "power_in"))
      (node (ref "U2") (pin "29_1") (pinfunction "GND_29_1") (pintype "power_in"))
      (node (ref "U2") (pin "29_2") (pinfunction "GND_29_2") (pintype "power_in"))
      (node (ref "U2") (pin "29_3") (pinfunction "GND_29_3") (pintype "power_in"))
      (node (ref "U2") (pin "29_4") (pinfunction "GND_29_4") (pintype "power_in"))
      (node (ref "U2") (pin "29_5") (pinfunction "GND_29_5") (pintype "power_in"))
      (node (ref "U2") (pin "29_6") (pinfunction "GND_29_6") (pintype "power_in"))
      (node (ref "U2") (pin "29_7") (pinfunction "GND_29_7") (pintype "power_in"))
      (node (ref "U2") (pin "29_8") (pinfunction "GND_29_8") (pintype "power_in"))
      (node (ref "U2") (pin "29_9") (pinfunction "GND_29_9") (pintype "power_in"))
      (node (ref "U3") (pin "13") (pinfunction "GND_13") (pintype "power_in"))
      (node (ref "U4") (pin "1") (pinfunction "CTG_1") (pintype "power_in"))
      (node (ref "U4") (pin "4") (pinfunction "GND_4") (pintype "power_in"))
      (node (ref "U4") (pin "6") (pinfunction "QSTRT_6") (pintype "input"))
      (node (ref "U4") (pin "9") (pinfunction "EP_9") (pintype "power_in"))
      (node (ref "U5") (pin "2") (pinfunction "VSS_2") (pintype "power_in"))
    )
    (net (code "14") (name "GPIO8") (class "Default")
      (node (ref "R1") (pin "2") (pinfunction "2_2") (pintype "passive"))
      (node (ref "U2") (pin "10") (pinfunction "IO8_10") (pintype "bidirectional"))
    )
    (net (code "15") (name "I2C_PW") (class "Default")
      (node (ref "C1") (pin "1") (pinfunction "1_1") (pintype "passive"))
      (node (ref "C2") (pin "1") (pinfunction "1_1") (pintype "passive"))
      (node (ref "R1_PINH") (pin "2") (pinfunction "2_2") (pintype "passive"))
      (node (ref "R2-PINH") (pin "2") (pinfunction "2_2") (pintype "passive"))
      (node (ref "SENSOR2") (pin "2") (pinfunction "CSB_2") (pintype "input"))
      (node (ref "SENSOR2") (pin "6") (pinfunction "VDDIO_6") (pintype "power_in"))
      (node (ref "SENSOR2") (pin "8") (pinfunction "VDD_8") (pintype "power_in"))
      (node (ref "U2") (pin "17") (pinfunction "IO19_17") (pintype "bidirectional"))
    )
    (net (code "16") (name "INT_RTC") (class "Default")
      (node (ref "INT_RTC") (pin "TP") (pinfunction "TP_TP") (pintype "input"))
      (node (ref "R1_PINH1") (pin "1") (pinfunction "1_1") (pintype "passive"))
      (node (ref "U2") (pin "8") (pinfunction "IO0_8") (pintype "bidirectional"))
      (node (ref "U3") (pin "3") (pinfunction "SQW/~{INT}_3") (pintype "output"))
    )
    (net (code "17") (name "IO{slash}BOOT") (class "Default")
      (node (ref "BOOT_BUTTON") (pin "3") (pinfunction "3_3") (pintype "passive"))
      (node (ref "BOOT_BUTTON") (pin "4") (pinfunction "4_4") (pintype "passive"))
      (node (ref "C6") (pin "1") (pinfunction "1_1") (pintype "passive"))
      (node (ref "R_BOOT") (pin "2") (pinfunction "2_2") (pintype "passive"))
      (node (ref "U2") (pin "15") (pinfunction "IO9_15") (pintype "bidirectional"))
    )
    (net (code "18") (name "IO{slash}CHANGE") (class "Default")
      (node (ref "C10") (pin "1") (pinfunction "1_1") (pintype "passive"))
      (node (ref "CHANGE_BUTTON") (pin "3") (pinfunction "3_3") (pintype "passive"))
      (node (ref "CHANGE_BUTTON") (pin "4") (pinfunction "4_4") (pintype "passive"))
      (node (ref "R_CHANGE") (pin "2") (pinfunction "2_2") (pintype "passive"))
      (node (ref "U2") (pin "23") (pinfunction "IO15_23") (pintype "bidirectional"))
    )
    (net (code "19") (name "MISO") (class "Default")
      (node (ref "D12") (pin "2") (pinfunction "2_2") (pintype "passive"))
      (node (ref "J4") (pin "P7") (pinfunction "DAT0_P7") (pintype "bidirectional"))
      (node (ref "MISO") (pin "TP") (pinfunction "TP_TP") (pintype "input"))
      (node (ref "R8") (pin "1") (pinfunction "1_1") (pintype "passive"))
      (node (ref "U1") (pin "2") (pinfunction "DO(IO1)_2") (pintype "bidirectional"))
      (node (ref "U2") (pin "27") (pinfunction "IO2_27") (pintype "bidirectional"))
    )
    (net (code "20") (name "MOSI") (class "Default")
      (node (ref "D11") (pin "2") (pinfunction "2_2") (pintype "passive"))
      (node (ref "J1") (pin "14") (pinfunction "14_14") (pintype "bidirectional"))
      (node (ref "J4") (pin "P3") (pinfunction "CMD_P3") (pintype "bidirectional"))
      (node (ref "MOSI") (pin "TP") (pinfunction "TP_TP") (pintype "input"))
      (node (ref "R7") (pin "1") (pinfunction "1_1") (pintype "passive"))
      (node (ref "U1") (pin "5") (pinfunction "DI(IO0)_5") (pintype "bidirectional"))
      (node (ref "U2") (pin "7") (pinfunction "IO7_7") (pintype "bidirectional"))
    )
    (net (code "21") (name "Net-(CHG_LED-PadC)") (class "Default")
      (node (ref "CHG_LED") (pin "C") (pinfunction "C_C") (pintype "passive"))
      (node (ref "R1_BAT") (pin "2") (pinfunction "2_2") (pintype "passive"))
    )
    (net (code "22") (name "Net-(D2-CATHODE)") (class "Default")
      (node (ref "C1_BAT1") (pin "1") (pinfunction "1_1") (pintype "passive"))
      (node (ref "D2") (pin "1") (pinfunction "CATHODE_1") (pintype "bidirectional"))
      (node (ref "IC4") (pin "1") (pinfunction "VIN_1") (pintype "bidirectional"))
      (node (ref "IC4") (pin "3") (pinfunction "CE_3") (pintype "bidirectional"))
      (node (ref "Q1") (pin "2") (pinfunction "S_2") (pintype "bidirectional"))
    )
    (net (code "23") (name "Net-(D3-A)") (class "Default")
      (node (ref "C4") (pin "1") (pinfunction "1_1") (pintype "passive"))
      (node (ref "D3") (pin "2") (pinfunction "A_2") (pintype "bidirectional"))
      (node (ref "D4") (pin "1") (pinfunction "K_1") (pintype "bidirectional"))
    )
    (net (code "24") (name "Net-(D7-CATHODE)") (class "Default")
      (node (ref "D7") (pin "1") (pinfunction "CATHODE_1") (pintype "bidirectional"))
      (node (ref "R_CAPACITOR") (pin "2") (pinfunction "2_2") (pintype "passive"))
    )
    (net (code "25") (name "Net-(EPD_C1-Pad1)") (class "Default")
      (node (ref "EPD_C1") (pin "1") (pinfunction "1_1") (pintype "passive"))
      (node (ref "J1") (pin "4") (pinfunction "4_4") (pintype "bidirectional"))
    )
    (net (code "26") (name "Net-(EPD_C2-Pad1)") (class "Default")
      (node (ref "EPD_C2") (pin "1") (pinfunction "1_1") (pintype "passive"))
      (node (ref "J1") (pin "5") (pinfunction "5_5") (pintype "bidirectional"))
    )
    (net (code "27") (name "Net-(EPD_C6-Pad2)") (class "Default")
      (node (ref "EPD_C6") (pin "2") (pinfunction "2_2") (pintype "passive"))
      (node (ref "J1") (pin "18") (pinfunction "18_18") (pintype "bidirectional"))
    )
    (net (code "28") (name "Net-(EPD_C7-Pad2)") (class "Default")
      (node (ref "EPD_C7") (pin "2") (pinfunction "2_2") (pintype "passive"))
      (node (ref "J1") (pin "19") (pinfunction "19_19") (pintype "bidirectional"))
    )
    (net (code "29") (name "Net-(EPD_C8-Pad2)") (class "Default")
      (node (ref "EPD_C8") (pin "2") (pinfunction "2_2") (pintype "passive"))
      (node (ref "J1") (pin "20") (pinfunction "20_20") (pintype "bidirectional"))
    )
    (net (code "30") (name "Net-(EPD_C10-Pad2)") (class "Default")
      (node (ref "EPD_C10") (pin "2") (pinfunction "2_2") (pintype "passive"))
      (node (ref "J1") (pin "22") (pinfunction "22_22") (pintype "bidirectional"))
    )
    (net (code "31") (name "Net-(EPD_C12-Pad2)") (class "Default")
      (node (ref "EPD_C12") (pin "2") (pinfunction "2_2") (pintype "passive"))
      (node (ref "J1") (pin "24") (pinfunction "24_24") (pintype "bidirectional"))
    )
    (net (code "32") (name "Net-(IC1-CT)") (class "Default")
      (node (ref "C_DELAY") (pin "1") (pinfunction "1_1") (pintype "passive"))
      (node (ref "IC1") (pin "5") (pinfunction "CT_5") (pintype "bidirectional"))
    )
    (net (code "33") (name "Net-(J2-PadA5)") (class "Default")
      (node (ref "J2") (pin "A5") (pinfunction "A5_A5") (pintype "bidirectional"))
      (node (ref "R2-USB1") (pin "2") (pinfunction "2_2") (pintype "passive"))
    )
    (net (code "34") (name "Net-(J2-PadB5)") (class "Default")
      (node (ref "J2") (pin "B5") (pinfunction "B5_B5") (pintype "bidirectional"))
      (node (ref "R2-USB") (pin "1") (pinfunction "1_1") (pintype "passive"))
    )
    (net (code "35") (name "Net-(U5-PROG)") (class "Default")
      (node (ref "R2_BAT") (pin "2") (pinfunction "2_2") (pintype "passive"))
      (node (ref "U5") (pin "5") (pinfunction "PROG_5") (pintype "input"))
    )
    (net (code "36") (name "Net-(U5-STAT)") (class "Default")
      (node (ref "R1_BAT") (pin "1") (pinfunction "1_1") (pintype "passive"))
      (node (ref "U5") (pin "1") (pinfunction "STAT_1") (pintype "output"))
    )
    (net (code "37") (name "PREVGH") (class "Default")
      (node (ref "D5") (pin "1") (pinfunction "K_1") (pintype "bidirectional"))
      (node (ref "EPD_C9") (pin "2") (pinfunction "2_2") (pintype "passive"))
      (node (ref "J1") (pin "21") (pinfunction "21_21") (pintype "bidirectional"))
    )
    (net (code "38") (name "PREVGL") (class "Default")
      (node (ref "D4") (pin "2") (pinfunction "A_2") (pintype "bidirectional"))
      (node (ref "EPD_C11") (pin "2") (pinfunction "2_2") (pintype "passive"))
      (node (ref "J1") (pin "23") (pinfunction "23_23") (pintype "bidirectional"))
    )
    (net (code "39") (name "RESE") (class "Default")
      (node (ref "J1") (pin "3") (pinfunction "3_3") (pintype "bidirectional"))
      (node (ref "Q3") (pin "2") (pinfunction "S_2") (pintype "bidirectional"))
      (node (ref "R3") (pin "1") (pinfunction "1_1") (pintype "passive"))
    )
    (net (code "40") (name "RESE'") (class "Default")
      (node (ref "R2") (pin "2") (pinfunction "2_2") (pintype "passive"))
      (node (ref "R3") (pin "2") (pinfunction "2_2") (pintype "passive"))
      (node (ref "SJ1") (pin "2") (pinfunction "2_2") (pintype "passive"))
    )
    (net (code "41") (name "RESET") (class "Default")
      (node (ref "C5") (pin "1") (pinfunction "1_1") (pintype "passive"))
      (node (ref "IC1") (pin "1") (pinfunction "VOUT_1") (pintype "bidirectional"))
      (node (ref "RESET_BUTTON") (pin "3") (pinfunction "3_3") (pintype "passive"))
      (node (ref "RESET_BUTTON") (pin "4") (pinfunction "4_4") (pintype "passive"))
      (node (ref "R_RESET") (pin "2") (pinfunction "2_2") (pintype "passive"))
      (node (ref "U2") (pin "3") (pinfunction "EN_3") (pintype "input"))
    )
    (net (code "42") (name "RTC_RST") (class "Default")
      (node (ref "U2") (pin "16") (pinfunction "IO18_16") (pintype "bidirectional"))
      (node (ref "U3") (pin "4") (pinfunction "~{RST}_4") (pintype "input"))
    )
    (net (code "43") (name "RX") (class "Default")
      (node (ref "RX") (pin "TP") (pinfunction "TP_TP") (pintype "input"))
      (node (ref "U2") (pin "24") (pinfunction "RXD0/GPIO17_24") (pintype "bidirectional"))
    )
    (net (code "44") (name "SCK") (class "Default")
      (node (ref "D10") (pin "2") (pinfunction "2_2") (pintype "passive"))
      (node (ref "J1") (pin "13") (pinfunction "13_13") (pintype "bidirectional"))
      (node (ref "J4") (pin "P5") (pinfunction "CLK_P5") (pintype "bidirectional"))
      (node (ref "R6") (pin "1") (pinfunction "1_1") (pintype "passive"))
      (node (ref "SCK") (pin "TP") (pinfunction "TP_TP") (pintype "input"))
      (node (ref "U1") (pin "6") (pinfunction "CLK_6") (pintype "input"))
      (node (ref "U2") (pin "6") (pinfunction "IO6_6") (pintype "bidirectional"))
    )
    (net (code "45") (name "SCL") (class "Default")
      (node (ref "J3") (pin "4") (pinfunction "4_4") (pintype "passive"))
      (node (ref "R2-PINH") (pin "1") (pinfunction "1_1") (pintype "passive"))
      (node (ref "SENSOR2") (pin "4") (pinfunction "SCK_4") (pintype "input"))
      (node (ref "U2") (pin "20") (pinfunction "IO22_20") (pintype "bidirectional"))
      (node (ref "U3") (pin "16") (pinfunction "SCL_16") (pintype "input"))
      (node (ref "U4") (pin "7") (pinfunction "SCL_7") (pintype "input"))
    )
    (net (code "46") (name "SDA") (class "Default")
      (node (ref "J3") (pin "3") (pinfunction "3_3") (pintype "passive"))
      (node (ref "R1_PINH") (pin "1") (pinfunction "1_1") (pintype "passive"))
      (node (ref "SENSOR2") (pin "3") (pinfunction "SDI_3") (pintype "bidirectional"))
      (node (ref "U2") (pin "19") (pinfunction "IO21_19") (pintype "bidirectional"))
      (node (ref "U3") (pin "15") (pinfunction "SDA_15") (pintype "bidirectional"))
      (node (ref "U4") (pin "8") (pinfunction "SDA_8") (pintype "bidirectional"))
    )
    (net (code "47") (name "SRC") (class "Default")
      (node (ref "C4") (pin "2") (pinfunction "2_2") (pintype "passive"))
      (node (ref "D5") (pin "2") (pinfunction "A_2") (pintype "bidirectional"))
      (node (ref "L1") (pin "1") (pinfunction "1_1") (pintype "passive"))
      (node (ref "Q3") (pin "3") (pinfunction "D_3") (pintype "bidirectional"))
    )
    (net (code "48") (name "SS_SD") (class "Default")
      (node (ref "D8") (pin "2") (pinfunction "2_2") (pintype "passive"))
      (node (ref "J4") (pin "P2") (pinfunction "CD/DAT3_P2") (pintype "bidirectional"))
      (node (ref "R10") (pin "1") (pinfunction "1_1") (pintype "passive"))
      (node (ref "U2") (pin "4") (pinfunction "IO4_4") (pintype "bidirectional"))
    )
    (net (code "49") (name "TX") (class "Default")
      (node (ref "TX") (pin "TP") (pinfunction "TP_TP") (pintype "input"))
      (node (ref "U2") (pin "25") (pinfunction "TXD0/GPIO16_25") (pintype "bidirectional"))
    )
    (net (code "50") (name "USB_D+") (class "Default")
      (node (ref "D1") (pin "1") (pinfunction "I/O1_1_1") (pintype "bidirectional"))
      (node (ref "U2") (pin "14") (pinfunction "IO13_14") (pintype "bidirectional"))
    )
    (net (code "51") (name "USB_D-") (class "Default")
      (node (ref "D1") (pin "3") (pinfunction "I/O2_1_3") (pintype "bidirectional"))
      (node (ref "U2") (pin "13") (pinfunction "IO12_13") (pintype "bidirectional"))
    )
    (net (code "52") (name "VBAT") (class "Default")
      (node (ref "C2_BAT") (pin "1") (pinfunction "1_1") (pintype "passive"))
      (node (ref "Q1") (pin "3") (pinfunction "D_3") (pintype "bidirectional"))
      (node (ref "U4") (pin "2") (pinfunction "CELL_2") (pintype "power_in"))
      (node (ref "U4") (pin "3") (pinfunction "VDD_3") (pintype "power_in"))
      (node (ref "U5") (pin "3") (pinfunction "VBAT_3") (pintype "power_in"))
      (node (ref "VBAT") (pin "TP") (pinfunction "TP_TP") (pintype "input"))
    )
    (net (code "53") (name "VBUS") (class "Default")
      (node (ref "C1_BAT") (pin "1") (pinfunction "1_1") (pintype "passive"))
      (node (ref "C4_USB") (pin "1") (pinfunction "1_1") (pintype "passive"))
      (node (ref "C5_USB") (pin "1") (pinfunction "1_1") (pintype "passive"))
      (node (ref "CHG_LED") (pin "A") (pinfunction "A_A") (pintype "passive"))
      (node (ref "D1") (pin "5") (pinfunction "VBUS_5") (pintype "bidirectional"))
      (node (ref "D2") (pin "2") (pinfunction "ANODE_2") (pintype "bidirectional"))
      (node (ref "PFMF.050.1") (pin "2") (pinfunction "2_2") (pintype "passive"))
      (node (ref "Q1") (pin "1") (pinfunction "G_1") (pintype "bidirectional"))
      (node (ref "R1_PWRUSB") (pin "2") (pinfunction "2_2") (pintype "passive"))
      (node (ref "U5") (pin "4") (pinfunction "VIN_4") (pintype "power_in"))
      (node (ref "VBUS") (pin "TP") (pinfunction "TP_TP") (pintype "input"))
    )
    (net (code "54") (name "VRTC") (class "Default")
      (node (ref "C10_SUPERCAP") (pin "2") (pinfunction "2_2") (pintype "passive"))
      (node (ref "C8") (pin "1") (pinfunction "1_1") (pintype "passive"))
      (node (ref "R_CAPACITOR") (pin "1") (pinfunction "1_1") (pintype "passive"))
      (node (ref "U3") (pin "14") (pinfunction "VBAT_14") (pintype "power_in"))
    )
    (net (code "55") (name "VUSB") (class "Default")
      (node (ref "J2") (pin "A4") (pinfunction "A4_A4") (pintype "bidirectional"))
      (node (ref "J2") (pin "A9") (pinfunction "A9_A9") (pintype "bidirectional"))
      (node (ref "J2") (pin "B4") (pinfunction "B4_B4") (pintype "bidirectional"))
      (node (ref "J2") (pin "B9") (pinfunction "B9_B9") (pintype "bidirectional"))
      (node (ref "PFMF.050.1") (pin "1") (pinfunction "1_1") (pintype "passive"))
    )
    (net (code "56") (name "unconnected-(IC1-NC-Pad4)") (class "Default")
      (node (ref "IC1") (pin "4") (pinfunction "NC_4") (pintype "no_connect"))
    )
    (net (code "57") (name "unconnected-(IC4-NC-Pad4)") (class "Default")
      (node (ref "IC4") (pin "4") (pinfunction "NC_4") (pintype "no_connect"))
    )
    (net (code "58") (name "unconnected-(J1-Pad1)") (class "Default")
      (node (ref "J1") (pin "1") (pinfunction "1_1") (pintype "bidirectional"))
    )
    (net (code "59") (name "unconnected-(J1-Pad6)") (class "Default")
      (node (ref "J1") (pin "6") (pinfunction "6_6") (pintype "bidirectional"))
    )
    (net (code "60") (name "unconnected-(J1-Pad7)") (class "Default")
      (node (ref "J1") (pin "7") (pinfunction "7_7") (pintype "bidirectional"))
    )
    (net (code "61") (name "unconnected-(J2-PadA8)") (class "Default")
      (node (ref "J2") (pin "A8") (pinfunction "A8_A8") (pintype "bidirectional"))
    )
    (net (code "62") (name "unconnected-(J2-PadB8)") (class "Default")
      (node (ref "J2") (pin "B8") (pinfunction "B8_B8") (pintype "bidirectional"))
    )
    (net (code "63") (name "unconnected-(J4-DAT1-PadP8)") (class "Default")
      (node (ref "J4") (pin "P8") (pinfunction "DAT1_P8") (pintype "bidirectional"))
    )
    (net (code "64") (name "unconnected-(J4-DAT2-PadP1)") (class "Default")
      (node (ref "J4") (pin "P1") (pinfunction "DAT2_P1") (pintype "bidirectional"))
    )
    (net (code "65") (name "unconnected-(J4-DETECTION_1-PadS1)") (class "Default")
      (node (ref "J4") (pin "S1") (pinfunction "DETECTION_1_S1") (pintype "bidirectional"))
    )
    (net (code "66") (name "unconnected-(J4-DETECTION_2-PadS2)") (class "Default")
      (node (ref "J4") (pin "S2") (pinfunction "DETECTION_2_S2") (pintype "bidirectional"))
    )
    (net (code "67") (name "unconnected-(U2-NC-Pad22)") (class "Default")
      (node (ref "U2") (pin "22") (pinfunction "NC_22") (pintype "no_connect"))
    )
    (net (code "68") (name "unconnected-(U4-~{ALERT}-Pad5)") (class "Default")
      (node (ref "U4") (pin "5") (pinfunction "~{ALERT}_5") (pintype "output"))
    )
  )
)
